# Access_Control_Signal_Relay_Switch.net
KiCad netlist of a schematic drawn in EasyEDA Pro
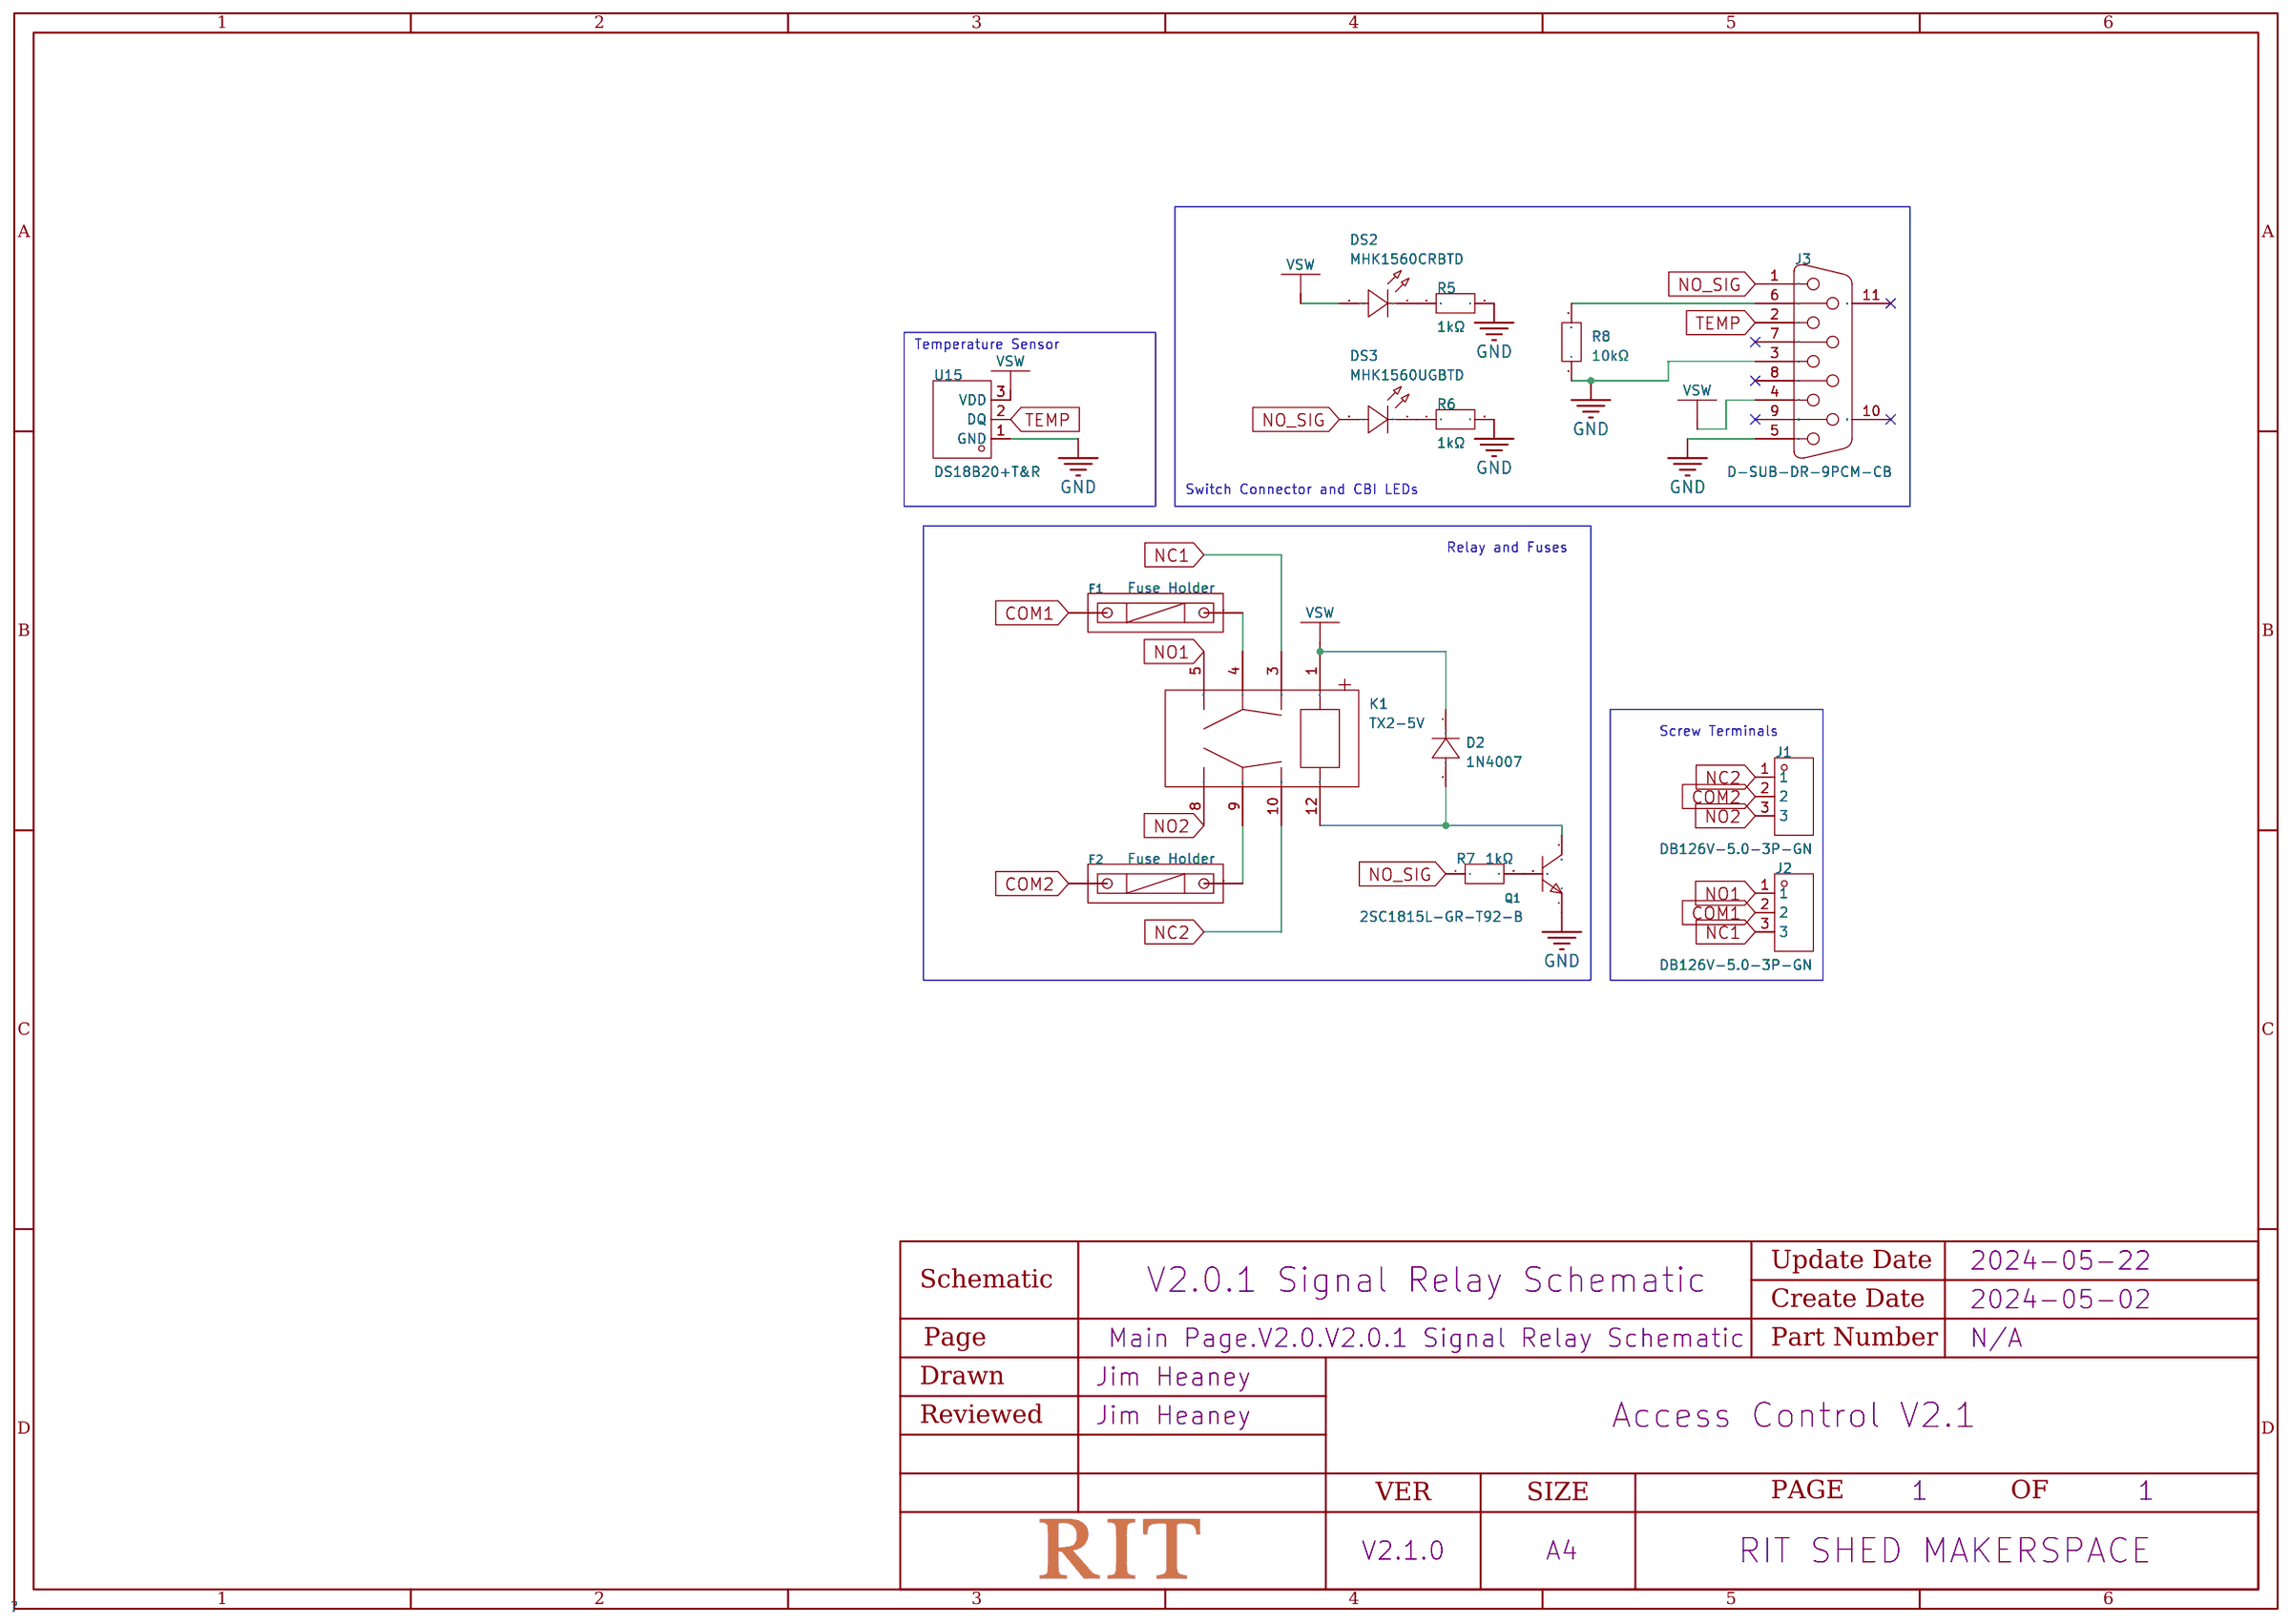
[diagram p0: schematic sheet]

(export (version "E")
  (design (tool "Eeschema 10.0.6"))
  (components
    (comp (ref "D2")
      (value "1N4007")
      (footprint "easyedapro:DO-41_BD2.4-L4.7-P8.70-D0.8-RD")
      (fields (field (name "Manufacturer") "GOODWORK(固得沃克)"))
      (libsource (lib "easyedapro") (part "1N4007_C2985028"))
    )
    (comp (ref "DS2")
      (value "MHK1560CRBTD")
      (footprint "easyedapro:LED-TH_MHK1560UGBTD")
      (fields (field (name "Manufacturer") "MEIHUA(美华)"))
      (libsource (lib "easyedapro") (part "MHK1560CGBTD"))
    )
    (comp (ref "DS3")
      (value "MHK1560UGBTD")
      (footprint "easyedapro:LED-TH_MHK1560UGBTD")
      (fields (field (name "Manufacturer") "MEIHUA(美华)"))
      (libsource (lib "easyedapro") (part "MHK1560UGBTD"))
    )
    (comp (ref "F1")
      (value "Fuse Holder")
      (footprint "easyedapro:FUSE-TH_L24.5-W9.8-P22.5")
      (description "Fuseholder Type:- Fuse Type:- Fuse Size:-")
      (fields (field (name "Manufacturer Part") "保险丝透明座") (field (name "Manufacturer") "xcfuse(旭程)"))
      (libsource (lib "easyedapro") (part "Fuse transparent seat"))
    )
    (comp (ref "F2")
      (value "Fuse Holder")
      (footprint "easyedapro:FUSE-TH_L24.5-W9.8-P22.5")
      (description "Fuseholder Type:- Fuse Type:- Fuse Size:-")
      (fields (field (name "Manufacturer Part") "保险丝透明座") (field (name "Manufacturer") "xcfuse(旭程)"))
      (libsource (lib "easyedapro") (part "Fuse transparent seat"))
    )
    (comp (ref "J1")
      (value "DB126V-5.0-3P-GN")
      (footprint "easyedapro:CONN-TH_3P-P5.00_DB126V-5.0-3P")
      (fields (field (name "Manufacturer") "DORABO(地博电气)"))
      (libsource (lib "easyedapro") (part "DB126V-5.0-3P"))
    )
    (comp (ref "J2")
      (value "DB126V-5.0-3P-GN")
      (footprint "easyedapro:CONN-TH_3P-P5.00_DB126V-5.0-3P")
      (fields (field (name "Manufacturer") "DORABO(地博电气)"))
      (libsource (lib "easyedapro") (part "DB126V-5.0-3P"))
    )
    (comp (ref "J3")
      (value "D-SUB-DR-9PCM-CB")
      (footprint "easyedapro:DB9-TH_ID09S33E4GV00LF")
      (fields (field (name "Manufacturer") "XUNPU(讯普)"))
      (libsource (lib "easyedapro") (part "D-SUB-DR-9PCM-CB"))
    )
    (comp (ref "K1")
      (value "TX2-5V")
      (footprint "easyedapro:RELAY-TH_TX2-3V")
      (fields (field (name "Manufacturer") "PANASONIC(松下)"))
      (libsource (lib "easyedapro") (part "TX2-5V"))
    )
    (comp (ref "Q1")
      (value "2SC1815L-GR-T92-B")
      (footprint "easyedapro:TO-92-3_L4.9-W3.7-P2.54-L")
      (fields (field (name "Manufacturer") "UTC(友顺)"))
      (libsource (lib "easyedapro") (part "2SC1815L-GR-T92-B"))
    )
    (comp (ref "R5")
      (value "1kΩ")
      (footprint "easyedapro:RES-TH_BD2.3-L6.5-P10.50-D0.5")
      (fields (field (name "Manufacturer Part") "MF1/4W-1KΩ±1%T52") (field (name "Manufacturer") "华星机电"))
      (libsource (lib "easyedapro") (part "MF1/4W-1KΩ±1%T52"))
    )
    (comp (ref "R6")
      (value "1kΩ")
      (footprint "easyedapro:RES-TH_BD2.3-L6.5-P10.50-D0.5")
      (fields (field (name "Manufacturer Part") "MF1/4W-1KΩ±1%T52") (field (name "Manufacturer") "华星机电"))
      (libsource (lib "easyedapro") (part "MF1/4W-1KΩ±1%T52"))
    )
    (comp (ref "R7")
      (value "1kΩ")
      (footprint "easyedapro:RES-TH_BD2.3-L6.5-P10.50-D0.5")
      (fields (field (name "Manufacturer Part") "MF1/4W-1KΩ±1%T52") (field (name "Manufacturer") "华星机电"))
      (libsource (lib "easyedapro") (part "MF1/4W-1KΩ±1%T52"))
    )
    (comp (ref "R8")
      (value "10kΩ")
      (footprint "easyedapro:RES-TH_BD2.7-L6.2-P10.20-D0.4")
      (fields (field (name "Manufacturer Part") "CR1/4W-10K±5%-ST26") (field (name "Manufacturer") "VO(翔胜)"))
      (libsource (lib "easyedapro") (part "CR1/4W-10K±5%-ST26"))
    )
    (comp (ref "U15")
      (value "DS18B20+T&R")
      (footprint "easyedapro:TO-92-3_L4.9-W3.7-P2.54-L")
      (description "Supply Voltage:3V~5.5V Supply Voltage:3V~5.5V")
      (fields (field (name "Manufacturer") "ADI(亚德诺)/MAXIM(美信)"))
      (libsource (lib "easyedapro") (part "DS18B20+T&R"))
    )
  )
  (nets
    (net (code "1") (name "COM1") (class "Default")
      (node (ref "F1") (pin "1") (pinfunction "1_1") (pintype "input"))
      (node (ref "J2") (pin "2") (pinfunction "2_2") (pintype "unspecified"))
    )
    (net (code "2") (name "COM2") (class "Default")
      (node (ref "F2") (pin "1") (pinfunction "1_1") (pintype "input"))
      (node (ref "J1") (pin "2") (pinfunction "2_2") (pintype "unspecified"))
    )
    (net (code "3") (name "GND") (class "Default")
      (node (ref "J3") (pin "3") (pinfunction "3_3") (pintype "input"))
      (node (ref "J3") (pin "5") (pinfunction "5_5") (pintype "input"))
      (node (ref "Q1") (pin "1") (pinfunction "E_1") (pintype "input"))
      (node (ref "R5") (pin "2") (pinfunction "2_2") (pintype "unspecified"))
      (node (ref "R6") (pin "2") (pinfunction "2_2") (pintype "unspecified"))
      (node (ref "R8") (pin "1") (pinfunction "1_1") (pintype "unspecified"))
      (node (ref "U15") (pin "1") (pinfunction "GND_1") (pintype "unspecified"))
    )
    (net (code "4") (name "NC1") (class "Default")
      (node (ref "J2") (pin "3") (pinfunction "3_3") (pintype "unspecified"))
      (node (ref "K1") (pin "3") (pinfunction "3_3") (pintype "input"))
    )
    (net (code "5") (name "NC2") (class "Default")
      (node (ref "J1") (pin "1") (pinfunction "1_1") (pintype "unspecified"))
      (node (ref "K1") (pin "10") (pinfunction "10_10") (pintype "input"))
    )
    (net (code "6") (name "NO1") (class "Default")
      (node (ref "J2") (pin "1") (pinfunction "1_1") (pintype "unspecified"))
      (node (ref "K1") (pin "5") (pinfunction "5_5") (pintype "input"))
    )
    (net (code "7") (name "NO2") (class "Default")
      (node (ref "J1") (pin "3") (pinfunction "3_3") (pintype "unspecified"))
      (node (ref "K1") (pin "8") (pinfunction "8_8") (pintype "input"))
    )
    (net (code "8") (name "NO_SIG") (class "Default")
      (node (ref "DS3") (pin "2") (pinfunction "A_2") (pintype "unspecified"))
      (node (ref "J3") (pin "1") (pinfunction "1_1") (pintype "input"))
      (node (ref "R7") (pin "1") (pinfunction "1_1") (pintype "unspecified"))
    )
    (net (code "9") (name "Net-(D2-A)") (class "Default")
      (node (ref "D2") (pin "2") (pinfunction "A_2") (pintype "unspecified"))
      (node (ref "K1") (pin "12") (pinfunction "12_12") (pintype "input"))
      (node (ref "Q1") (pin "2") (pinfunction "C_2") (pintype "input"))
    )
    (net (code "10") (name "Net-(DS2-K)") (class "Default")
      (node (ref "DS2") (pin "1") (pinfunction "K_1") (pintype "unspecified"))
      (node (ref "R5") (pin "1") (pinfunction "1_1") (pintype "unspecified"))
    )
    (net (code "11") (name "Net-(DS3-K)") (class "Default")
      (node (ref "DS3") (pin "1") (pinfunction "K_1") (pintype "unspecified"))
      (node (ref "R6") (pin "1") (pinfunction "1_1") (pintype "unspecified"))
    )
    (net (code "12") (name "Net-(F1-Pad2)") (class "Default")
      (node (ref "F1") (pin "2") (pinfunction "2_2") (pintype "input"))
      (node (ref "K1") (pin "4") (pinfunction "4_4") (pintype "input"))
    )
    (net (code "13") (name "Net-(F2-Pad2)") (class "Default")
      (node (ref "F2") (pin "2") (pinfunction "2_2") (pintype "input"))
      (node (ref "K1") (pin "9") (pinfunction "9_9") (pintype "input"))
    )
    (net (code "14") (name "Net-(J3-Pad6)") (class "Default")
      (node (ref "J3") (pin "6") (pinfunction "6_6") (pintype "input"))
      (node (ref "R8") (pin "2") (pinfunction "2_2") (pintype "unspecified"))
    )
    (net (code "15") (name "Net-(Q1-B)") (class "Default")
      (node (ref "Q1") (pin "3") (pinfunction "B_3") (pintype "input"))
      (node (ref "R7") (pin "2") (pinfunction "2_2") (pintype "unspecified"))
    )
    (net (code "16") (name "TEMP") (class "Default")
      (node (ref "J3") (pin "2") (pinfunction "2_2") (pintype "input"))
      (node (ref "U15") (pin "2") (pinfunction "DQ_2") (pintype "unspecified"))
    )
    (net (code "17") (name "VSW") (class "Default")
      (node (ref "D2") (pin "1") (pinfunction "K_1") (pintype "unspecified"))
      (node (ref "DS2") (pin "2") (pinfunction "A_2") (pintype "unspecified"))
      (node (ref "J3") (pin "4") (pinfunction "4_4") (pintype "input"))
      (node (ref "K1") (pin "1") (pinfunction "1_1") (pintype "input"))
      (node (ref "U15") (pin "3") (pinfunction "VDD_3") (pintype "unspecified"))
    )
    (net (code "18") (name "unconnected-(J3-MH1-Pad10)") (class "Default")
      (node (ref "J3") (pin "10") (pinfunction "MH1_10") (pintype "input+no_connect"))
    )
    (net (code "19") (name "unconnected-(J3-MH2-Pad11)") (class "Default")
      (node (ref "J3") (pin "11") (pinfunction "MH2_11") (pintype "input+no_connect"))
    )
    (net (code "20") (name "unconnected-(J3-Pad7)") (class "Default")
      (node (ref "J3") (pin "7") (pinfunction "7_7") (pintype "input+no_connect"))
    )
    (net (code "21") (name "unconnected-(J3-Pad8)") (class "Default")
      (node (ref "J3") (pin "8") (pinfunction "8_8") (pintype "input+no_connect"))
    )
    (net (code "22") (name "unconnected-(J3-Pad9)") (class "Default")
      (node (ref "J3") (pin "9") (pinfunction "9_9") (pintype "input+no_connect"))
    )
  )
)
